# Seeeduino_v3_0.net
KiCad netlist of a schematic drawn in EAGLE
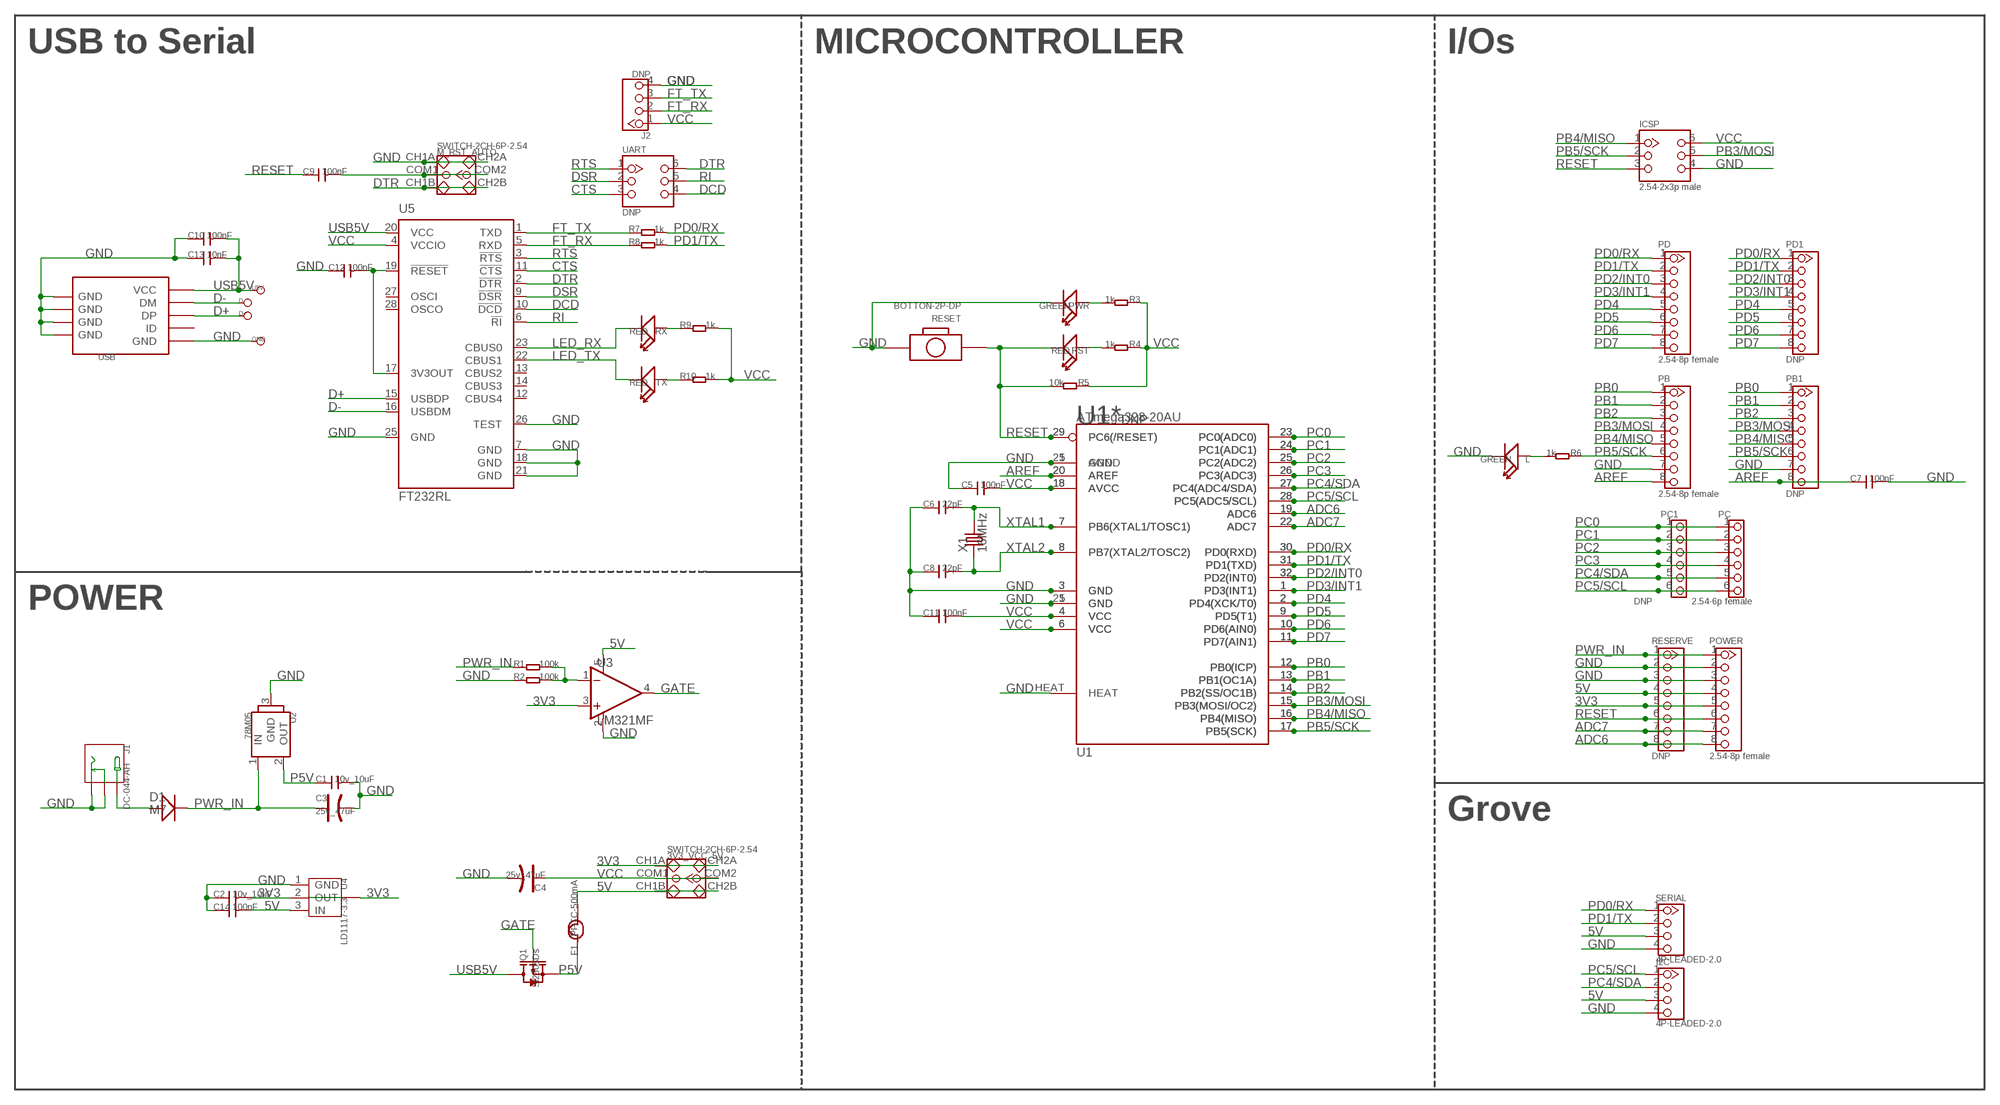
[diagram p0: schematic, sheet 1]

(export (version "E")
  (design (tool "Eeschema 10.0.6"))
  (components
    (comp (ref "3V3_VCC_5V")
      (value "SWITCH-2CH-6P-2.54")
      (footprint "eagle-import:6P-2CH-2.54-7.6X3.0")
      (libsource (lib "eagle-import") (part "SWITCH-2CH-6P"))
    )
    (comp (ref "C1")
      (value "10v_10uF")
      (footprint "eagle-import:0805")
      (libsource (lib "eagle-import") (part "C-0805"))
    )
    (comp (ref "C2")
      (value "10v_10uF")
      (footprint "eagle-import:0805")
      (libsource (lib "eagle-import") (part "C-0805"))
    )
    (comp (ref "C3")
      (value "25v_47uF")
      (footprint "eagle-import:ELECTRO-SMD-C-6MM")
      (libsource (lib "eagle-import") (part "CAP-ELECTRO-C"))
    )
    (comp (ref "C4")
      (value "25v_47uF")
      (footprint "eagle-import:ELECTRO-SMD-C-6MM")
      (libsource (lib "eagle-import") (part "CAP-ELECTRO-C"))
    )
    (comp (ref "C5")
      (value "100nF")
      (footprint "eagle-import:0603")
      (libsource (lib "eagle-import") (part "C-0603"))
    )
    (comp (ref "C6")
      (value "22pF")
      (footprint "eagle-import:0603")
      (libsource (lib "eagle-import") (part "C-0603"))
    )
    (comp (ref "C7")
      (value "100nF")
      (footprint "eagle-import:0603")
      (libsource (lib "eagle-import") (part "C-0603"))
    )
    (comp (ref "C8")
      (value "22pF")
      (footprint "eagle-import:0603")
      (libsource (lib "eagle-import") (part "C-0603"))
    )
    (comp (ref "C9")
      (value "100nF")
      (footprint "eagle-import:0603")
      (libsource (lib "eagle-import") (part "C-0603"))
    )
    (comp (ref "C10")
      (value "100nF")
      (footprint "eagle-import:0603")
      (libsource (lib "eagle-import") (part "C-0603"))
    )
    (comp (ref "C11")
      (value "100nF")
      (footprint "eagle-import:0603")
      (libsource (lib "eagle-import") (part "C-0603"))
    )
    (comp (ref "C12")
      (value "100nF")
      (footprint "eagle-import:0603")
      (libsource (lib "eagle-import") (part "C-0603"))
    )
    (comp (ref "C13")
      (value "10nF")
      (footprint "eagle-import:0603")
      (libsource (lib "eagle-import") (part "C-0603"))
    )
    (comp (ref "C14")
      (value "100nF")
      (footprint "eagle-import:0603")
      (libsource (lib "eagle-import") (part "C-0603"))
    )
    (comp (ref "D+")
      (value "TEST_POINT_SIZE_3030")
      (footprint "eagle-import:TP_3535")
      (libsource (lib "eagle-import") (part "TEST_POINT_SIZE_3030"))
    )
    (comp (ref "D-")
      (value "TEST_POINT_SIZE_3030")
      (footprint "eagle-import:TP_3535")
      (libsource (lib "eagle-import") (part "TEST_POINT_SIZE_3030"))
    )
    (comp (ref "D1")
      (value "M7")
      (footprint "eagle-import:D2010")
      (libsource (lib "eagle-import") (part "D-SMA"))
    )
    (comp (ref "F1")
      (value "PPTC-500mA")
      (footprint "eagle-import:1206")
      (libsource (lib "eagle-import") (part "FUSE"))
    )
    (comp (ref "GND")
      (value "TEST_POINT_SIZE_3030")
      (footprint "eagle-import:TP_3535")
      (libsource (lib "eagle-import") (part "TEST_POINT_SIZE_3030"))
    )
    (comp (ref "I2C")
      (value "4P-LEADED-2.0")
      (footprint "eagle-import:4P-LEADED-2.0")
      (libsource (lib "eagle-import") (part "TWIG-2.0-LEADED"))
    )
    (comp (ref "ICSP")
      (value "2.54-2x3p male")
      (footprint "eagle-import:2X3P-2.54")
      (libsource (lib "eagle-import") (part "HEADER-2X3P-2.54"))
    )
    (comp (ref "J1")
      (value "DC-044-AH")
      (footprint "eagle-import:DC-404")
      (libsource (lib "eagle-import") (part "DC-044"))
    )
    (comp (ref "J2")
      (value "DNP")
      (footprint "eagle-import:CK_1X4")
      (libsource (lib "eagle-import") (part "CK_1X4_DD"))
    )
    (comp (ref "L")
      (value "GREEN")
      (footprint "eagle-import:LED-0603")
      (libsource (lib "eagle-import") (part "LED'0603'"))
    )
    (comp (ref "M_RST_AUTO")
      (value "SWITCH-2CH-6P-2.54")
      (footprint "eagle-import:6P-2CH-2.54-7.6X3.0")
      (libsource (lib "eagle-import") (part "SWITCH-2CH-6P"))
    )
    (comp (ref "PB")
      (value "2.54-8p female")
      (footprint "eagle-import:8P-2.54")
      (libsource (lib "eagle-import") (part "HEADER-8P-2.54"))
    )
    (comp (ref "PB1")
      (value "DNP")
      (footprint "eagle-import:8P-2.54")
      (libsource (lib "eagle-import") (part "HEADER-8P-2.54"))
    )
    (comp (ref "PC")
      (value "2.54-6p female")
      (footprint "eagle-import:6P-2.54-65_35MIL")
      (libsource (lib "eagle-import") (part "HEADER-6P-65/35MIL"))
    )
    (comp (ref "PC1")
      (value "DNP")
      (footprint "eagle-import:6P-2.54-65_35MIL")
      (libsource (lib "eagle-import") (part "HEADER-6P-65/35MIL"))
    )
    (comp (ref "PD")
      (value "2.54-8p female")
      (footprint "eagle-import:8P-2.54")
      (libsource (lib "eagle-import") (part "HEADER-8P-2.54"))
    )
    (comp (ref "PD1")
      (value "DNP")
      (footprint "eagle-import:8P-2.54")
      (libsource (lib "eagle-import") (part "HEADER-8P-2.54"))
    )
    (comp (ref "POWER")
      (value "2.54-8p female")
      (footprint "eagle-import:8P-2.54")
      (libsource (lib "eagle-import") (part "HEADER-8P-2.54"))
    )
    (comp (ref "PWR")
      (value "GREEN")
      (footprint "eagle-import:LED-0603")
      (libsource (lib "eagle-import") (part "LED'0603'"))
    )
    (comp (ref "Q1")
      (value "Si2305Ds")
      (footprint "eagle-import:SOT23")
      (libsource (lib "eagle-import") (part "MOSFET-P-SOT23"))
    )
    (comp (ref "R1")
      (value "100k")
      (footprint "eagle-import:0603")
      (libsource (lib "eagle-import") (part "R-0603"))
    )
    (comp (ref "R2")
      (value "100k")
      (footprint "eagle-import:0603")
      (libsource (lib "eagle-import") (part "R-0603"))
    )
    (comp (ref "R3")
      (value "1k")
      (footprint "eagle-import:0603")
      (libsource (lib "eagle-import") (part "R-0603"))
    )
    (comp (ref "R4")
      (value "1k")
      (footprint "eagle-import:0603")
      (libsource (lib "eagle-import") (part "R-0603"))
    )
    (comp (ref "R5")
      (value "10k")
      (footprint "eagle-import:0603")
      (libsource (lib "eagle-import") (part "R-0603"))
    )
    (comp (ref "R6")
      (value "1k")
      (footprint "eagle-import:0603")
      (libsource (lib "eagle-import") (part "R-0603"))
    )
    (comp (ref "R7")
      (value "1k")
      (footprint "eagle-import:0603")
      (libsource (lib "eagle-import") (part "R-0603"))
    )
    (comp (ref "R8")
      (value "1k")
      (footprint "eagle-import:0603")
      (libsource (lib "eagle-import") (part "R-0603"))
    )
    (comp (ref "R9")
      (value "1k")
      (footprint "eagle-import:0603")
      (libsource (lib "eagle-import") (part "R-0603"))
    )
    (comp (ref "R10")
      (value "1k")
      (footprint "eagle-import:0603")
      (libsource (lib "eagle-import") (part "R-0603"))
    )
    (comp (ref "RESERVE")
      (value "DNP")
      (footprint "eagle-import:8P-2.54")
      (libsource (lib "eagle-import") (part "HEADER-8P-2.54"))
    )
    (comp (ref "RESET")
      (value "BOTTON-2P-DP")
      (footprint "eagle-import:2P-7.62X3.56-90D")
      (libsource (lib "eagle-import") (part "BOTTON-2P-90"))
    )
    (comp (ref "RST")
      (value "RED")
      (footprint "eagle-import:LED-0603")
      (libsource (lib "eagle-import") (part "LED'0603'"))
    )
    (comp (ref "RX")
      (value "RED")
      (footprint "eagle-import:LED-0603")
      (libsource (lib "eagle-import") (part "LED'0603'"))
    )
    (comp (ref "SERIAL")
      (value "4P-LEADED-2.0")
      (footprint "eagle-import:4P-LEADED-2.0")
      (libsource (lib "eagle-import") (part "TWIG-2.0-LEADED"))
    )
    (comp (ref "TX")
      (value "RED")
      (footprint "eagle-import:LED-0603")
      (libsource (lib "eagle-import") (part "LED'0603'"))
    )
    (comp (ref "U1")
      (value "ATmega328-20AU")
      (footprint "eagle-import:TQFP32")
      (libsource (lib "eagle-import") (part "ATMEGA168"))
    )
    (comp (ref "U1*")
      (value "DNP")
      (footprint "eagle-import:MLF32X")
      (libsource (lib "eagle-import") (part "MEGA8"))
    )
    (comp (ref "U2")
      (value "78M05")
      (footprint "eagle-import:TO252")
      (libsource (lib "eagle-import") (part "78M05-TO252"))
    )
    (comp (ref "U3")
      (value "LM321MF")
      (footprint "eagle-import:SOT23-5")
      (libsource (lib "eagle-import") (part "LM321"))
    )
    (comp (ref "U4")
      (value "LD1117-3.3")
      (footprint "eagle-import:SOT89")
      (libsource (lib "eagle-import") (part "LD1117SOT89"))
    )
    (comp (ref "U5")
      (value "FT232RL")
      (footprint "eagle-import:SSOP28")
      (libsource (lib "eagle-import") (part "FT232RL"))
    )
    (comp (ref "U5V")
      (value "TEST_POINT_SIZE_3030")
      (footprint "eagle-import:TP_3535")
      (libsource (lib "eagle-import") (part "TEST_POINT_SIZE_3030"))
    )
    (comp (ref "UART")
      (value "DNP")
      (footprint "eagle-import:2X3P-2.54")
      (libsource (lib "eagle-import") (part "HEADER-2X3P-2.54"))
    )
    (comp (ref "USB")
      (value "USB-MINIUSB-5P-STRONG")
      (footprint "eagle-import:MINI-SMD-5P")
      (libsource (lib "eagle-import") (part "USB-MINIUSB-5P-STRONG"))
    )
    (comp (ref "X1")
      (value "16MHz")
      (footprint "eagle-import:HC49_S")
      (libsource (lib "eagle-import") (part "CRYSTAL-HC49S"))
    )
  )
  (nets
    (net (code "1") (name "/3V3") (class "Default")
      (node (ref "3V3_VCC_5V") (pin "CH1A") (pinfunction "CH1A_CH1A") (pintype "bidirectional"))
      (node (ref "3V3_VCC_5V") (pin "CH2A") (pinfunction "CH2A_CH2A") (pintype "bidirectional"))
      (node (ref "C2") (pin "2") (pinfunction "2_2") (pintype "passive"))
      (node (ref "POWER") (pin "5") (pinfunction "5_5") (pintype "bidirectional"))
      (node (ref "RESERVE") (pin "5") (pinfunction "5_5") (pintype "bidirectional"))
      (node (ref "U3") (pin "3") (pinfunction "IN+_3") (pintype "input"))
      (node (ref "U4") (pin "2") (pinfunction "OUT_2") (pintype "bidirectional"))
      (node (ref "U4") (pin "4") (pinfunction "TAB_4") (pintype "bidirectional"))
    )
    (net (code "2") (name "/5V") (class "Default")
      (node (ref "3V3_VCC_5V") (pin "CH1B") (pinfunction "CH1B_CH1B") (pintype "bidirectional"))
      (node (ref "3V3_VCC_5V") (pin "CH2B") (pinfunction "CH2B_CH2B") (pintype "bidirectional"))
      (node (ref "C14") (pin "2") (pinfunction "2_2") (pintype "passive"))
      (node (ref "F1") (pin "2") (pinfunction "2_2") (pintype "bidirectional"))
      (node (ref "I2C") (pin "3") (pinfunction "3_3") (pintype "bidirectional"))
      (node (ref "POWER") (pin "4") (pinfunction "4_4") (pintype "bidirectional"))
      (node (ref "RESERVE") (pin "4") (pinfunction "4_4") (pintype "bidirectional"))
      (node (ref "SERIAL") (pin "3") (pinfunction "3_3") (pintype "bidirectional"))
      (node (ref "U3") (pin "5") (pinfunction "V+_5") (pintype "power_in"))
      (node (ref "U4") (pin "3") (pinfunction "IN_3") (pintype "bidirectional"))
    )
    (net (code "3") (name "/ADC6") (class "Default")
      (node (ref "POWER") (pin "8") (pinfunction "8_8") (pintype "bidirectional"))
      (node (ref "RESERVE") (pin "8") (pinfunction "8_8") (pintype "bidirectional"))
      (node (ref "U1") (pin "19") (pinfunction "ADC6_19") (pintype "bidirectional"))
      (node (ref "U1*") (pin "19") (pinfunction "ADC6_19") (pintype "bidirectional"))
    )
    (net (code "4") (name "/ADC7") (class "Default")
      (node (ref "POWER") (pin "7") (pinfunction "7_7") (pintype "bidirectional"))
      (node (ref "RESERVE") (pin "7") (pinfunction "7_7") (pintype "bidirectional"))
      (node (ref "U1") (pin "22") (pinfunction "ADC7_22") (pintype "bidirectional"))
      (node (ref "U1*") (pin "22") (pinfunction "ADC7_22") (pintype "bidirectional"))
    )
    (net (code "5") (name "/AREF") (class "Default")
      (node (ref "C7") (pin "1") (pinfunction "1_1") (pintype "passive"))
      (node (ref "PB") (pin "8") (pinfunction "8_8") (pintype "bidirectional"))
      (node (ref "PB1") (pin "8") (pinfunction "8_8") (pintype "bidirectional"))
      (node (ref "U1") (pin "20") (pinfunction "AREF_20") (pintype "bidirectional"))
      (node (ref "U1*") (pin "20") (pinfunction "AREF_20") (pintype "bidirectional"))
    )
    (net (code "6") (name "/CTS") (class "Default")
      (node (ref "U5") (pin "11") (pinfunction "~{CTS}_11") (pintype "input"))
      (node (ref "UART") (pin "3") (pinfunction "3_3") (pintype "bidirectional"))
    )
    (net (code "7") (name "/D+") (class "Default")
      (node (ref "D+") (pin "T") (pinfunction "T_T") (pintype "bidirectional"))
      (node (ref "U5") (pin "15") (pinfunction "USBDP_15") (pintype "input"))
      (node (ref "USB") (pin "3") (pinfunction "DP_3") (pintype "bidirectional"))
    )
    (net (code "8") (name "/D-") (class "Default")
      (node (ref "D-") (pin "T") (pinfunction "T_T") (pintype "bidirectional"))
      (node (ref "U5") (pin "16") (pinfunction "USBDM_16") (pintype "input"))
      (node (ref "USB") (pin "2") (pinfunction "DM_2") (pintype "bidirectional"))
    )
    (net (code "9") (name "/DCD") (class "Default")
      (node (ref "U5") (pin "10") (pinfunction "~{DCD}_10") (pintype "input"))
      (node (ref "UART") (pin "4") (pinfunction "4_4") (pintype "bidirectional"))
    )
    (net (code "10") (name "/DSR") (class "Default")
      (node (ref "U5") (pin "9") (pinfunction "~{DSR}_9") (pintype "input"))
      (node (ref "UART") (pin "2") (pinfunction "2_2") (pintype "bidirectional"))
    )
    (net (code "11") (name "/DTR") (class "Default")
      (node (ref "M_RST_AUTO") (pin "CH1B") (pinfunction "CH1B_CH1B") (pintype "bidirectional"))
      (node (ref "M_RST_AUTO") (pin "CH2B") (pinfunction "CH2B_CH2B") (pintype "bidirectional"))
      (node (ref "U5") (pin "2") (pinfunction "~{DTR}_2") (pintype "input"))
      (node (ref "UART") (pin "6") (pinfunction "6_6") (pintype "bidirectional"))
    )
    (net (code "12") (name "/FT_RX") (class "Default")
      (node (ref "J2") (pin "2") (pinfunction "P$2_2") (pintype "bidirectional"))
      (node (ref "R8") (pin "1") (pinfunction "1_1") (pintype "passive"))
      (node (ref "U5") (pin "5") (pinfunction "RXD_5") (pintype "input"))
    )
    (net (code "13") (name "/FT_TX") (class "Default")
      (node (ref "J2") (pin "3") (pinfunction "P$3_3") (pintype "bidirectional"))
      (node (ref "R7") (pin "1") (pinfunction "1_1") (pintype "passive"))
      (node (ref "U5") (pin "1") (pinfunction "TXD_1") (pintype "input"))
    )
    (net (code "14") (name "/GATE") (class "Default")
      (node (ref "Q1") (pin "1") (pinfunction "G_1") (pintype "passive"))
      (node (ref "U3") (pin "4") (pinfunction "OUT_4") (pintype "output"))
    )
    (net (code "15") (name "/GND") (class "Default")
      (node (ref "C1") (pin "2") (pinfunction "2_2") (pintype "passive"))
      (node (ref "C10") (pin "1") (pinfunction "1_1") (pintype "passive"))
      (node (ref "C11") (pin "1") (pinfunction "1_1") (pintype "passive"))
      (node (ref "C12") (pin "1") (pinfunction "1_1") (pintype "passive"))
      (node (ref "C13") (pin "1") (pinfunction "1_1") (pintype "passive"))
      (node (ref "C14") (pin "1") (pinfunction "1_1") (pintype "passive"))
      (node (ref "C2") (pin "1") (pinfunction "1_1") (pintype "passive"))
      (node (ref "C3") (pin "-") (pinfunction "-_-") (pintype "passive"))
      (node (ref "C4") (pin "-") (pinfunction "-_-") (pintype "passive"))
      (node (ref "C5") (pin "1") (pinfunction "1_1") (pintype "passive"))
      (node (ref "C6") (pin "1") (pinfunction "1_1") (pintype "passive"))
      (node (ref "C7") (pin "2") (pinfunction "2_2") (pintype "passive"))
      (node (ref "C8") (pin "1") (pinfunction "1_1") (pintype "passive"))
      (node (ref "GND") (pin "T") (pinfunction "T_T") (pintype "bidirectional"))
      (node (ref "I2C") (pin "4") (pinfunction "4_4") (pintype "bidirectional"))
      (node (ref "ICSP") (pin "4") (pinfunction "4_4") (pintype "bidirectional"))
      (node (ref "J1") (pin "-") (pinfunction "-_-") (pintype "bidirectional"))
      (node (ref "J1") (pin "CDN") (pinfunction "CDN_CDN") (pintype "bidirectional"))
      (node (ref "J2") (pin "4") (pinfunction "P$4_4") (pintype "bidirectional"))
      (node (ref "L") (pin "-") (pinfunction "-_-") (pintype "passive"))
      (node (ref "M_RST_AUTO") (pin "CH1A") (pinfunction "CH1A_CH1A") (pintype "bidirectional"))
      (node (ref "M_RST_AUTO") (pin "CH2A") (pinfunction "CH2A_CH2A") (pintype "bidirectional"))
      (node (ref "PB") (pin "7") (pinfunction "7_7") (pintype "bidirectional"))
      (node (ref "PB1") (pin "7") (pinfunction "7_7") (pintype "bidirectional"))
      (node (ref "POWER") (pin "2") (pinfunction "2_2") (pintype "bidirectional"))
      (node (ref "POWER") (pin "3") (pinfunction "3_3") (pintype "bidirectional"))
      (node (ref "PWR") (pin "-") (pinfunction "-_-") (pintype "passive"))
      (node (ref "R2") (pin "1") (pinfunction "1_1") (pintype "passive"))
      (node (ref "RESERVE") (pin "2") (pinfunction "2_2") (pintype "bidirectional"))
      (node (ref "RESERVE") (pin "3") (pinfunction "3_3") (pintype "bidirectional"))
      (node (ref "RESET") (pin "P$2") (pinfunction "2_P$2") (pintype "bidirectional"))
      (node (ref "SERIAL") (pin "4") (pinfunction "4_4") (pintype "bidirectional"))
      (node (ref "U1") (pin "21") (pinfunction "GND_21") (pintype "bidirectional"))
      (node (ref "U1") (pin "3") (pinfunction "GND_3") (pintype "bidirectional"))
      (node (ref "U1") (pin "5") (pinfunction "GND_5") (pintype "bidirectional"))
      (node (ref "U1*") (pin "21") (pinfunction "AGND_21") (pintype "bidirectional"))
      (node (ref "U1*") (pin "3") (pinfunction "GND_3") (pintype "bidirectional"))
      (node (ref "U1*") (pin "5") (pinfunction "GND_5") (pintype "bidirectional"))
      (node (ref "U1*") (pin "HEAT") (pinfunction "HEAT_HEAT") (pintype "bidirectional"))
      (node (ref "U2") (pin "3") (pinfunction "GND_3") (pintype "bidirectional"))
      (node (ref "U3") (pin "2") (pinfunction "V-_2") (pintype "power_in"))
      (node (ref "U4") (pin "1") (pinfunction "GND_1") (pintype "bidirectional"))
      (node (ref "U5") (pin "18") (pinfunction "GND_18") (pintype "input"))
      (node (ref "U5") (pin "21") (pinfunction "GND_21") (pintype "input"))
      (node (ref "U5") (pin "25") (pinfunction "GND_25") (pintype "input"))
      (node (ref "U5") (pin "26") (pinfunction "TEST_26") (pintype "input"))
      (node (ref "U5") (pin "7") (pinfunction "GND_7") (pintype "input"))
      (node (ref "USB") (pin "5") (pinfunction "GND_5") (pintype "bidirectional"))
      (node (ref "USB") (pin "GND@1") (pinfunction "GND_GND@1") (pintype "bidirectional"))
      (node (ref "USB") (pin "GND@2") (pinfunction "GND_GND@2") (pintype "bidirectional"))
      (node (ref "USB") (pin "GND@3") (pinfunction "GND_GND@3") (pintype "bidirectional"))
      (node (ref "USB") (pin "GND@4") (pinfunction "GND_GND@4") (pintype "bidirectional"))
    )
    (net (code "16") (name "/LED_RX") (class "Default")
      (node (ref "RX") (pin "-") (pinfunction "-_-") (pintype "passive"))
      (node (ref "U5") (pin "23") (pinfunction "CBUS0_23") (pintype "input"))
    )
    (net (code "17") (name "/LED_TX") (class "Default")
      (node (ref "TX") (pin "-") (pinfunction "-_-") (pintype "passive"))
      (node (ref "U5") (pin "22") (pinfunction "CBUS1_22") (pintype "input"))
    )
    (net (code "18") (name "/P5V") (class "Default")
      (node (ref "C1") (pin "1") (pinfunction "1_1") (pintype "passive"))
      (node (ref "F1") (pin "1") (pinfunction "1_1") (pintype "bidirectional"))
      (node (ref "Q1") (pin "2") (pinfunction "S_2") (pintype "passive"))
      (node (ref "U2") (pin "2") (pinfunction "OUT_2") (pintype "bidirectional"))
    )
    (net (code "19") (name "/PB0") (class "Default")
      (node (ref "PB") (pin "1") (pinfunction "1_1") (pintype "bidirectional"))
      (node (ref "PB1") (pin "1") (pinfunction "1_1") (pintype "bidirectional"))
      (node (ref "U1") (pin "12") (pinfunction "PB0(ICP)_12") (pintype "bidirectional"))
      (node (ref "U1*") (pin "12") (pinfunction "PB0(ICP)_12") (pintype "bidirectional"))
    )
    (net (code "20") (name "/PB1") (class "Default")
      (node (ref "PB") (pin "2") (pinfunction "2_2") (pintype "bidirectional"))
      (node (ref "PB1") (pin "2") (pinfunction "2_2") (pintype "bidirectional"))
      (node (ref "U1") (pin "13") (pinfunction "PB1(OC1A)_13") (pintype "bidirectional"))
      (node (ref "U1*") (pin "13") (pinfunction "PB1(OC1A)_13") (pintype "bidirectional"))
    )
    (net (code "21") (name "/PB2") (class "Default")
      (node (ref "PB") (pin "3") (pinfunction "3_3") (pintype "bidirectional"))
      (node (ref "PB1") (pin "3") (pinfunction "3_3") (pintype "bidirectional"))
      (node (ref "U1") (pin "14") (pinfunction "PB2(SS/OC1B)_14") (pintype "bidirectional"))
      (node (ref "U1*") (pin "14") (pinfunction "PB2(SS/OC1B)_14") (pintype "bidirectional"))
    )
    (net (code "22") (name "/PB3{slash}MOSI") (class "Default")
      (node (ref "ICSP") (pin "5") (pinfunction "5_5") (pintype "bidirectional"))
      (node (ref "PB") (pin "4") (pinfunction "4_4") (pintype "bidirectional"))
      (node (ref "PB1") (pin "4") (pinfunction "4_4") (pintype "bidirectional"))
      (node (ref "U1") (pin "15") (pinfunction "PB3(MOSI/OC2)_15") (pintype "bidirectional"))
      (node (ref "U1*") (pin "15") (pinfunction "PB3(MOSI/OC2)_15") (pintype "bidirectional"))
    )
    (net (code "23") (name "/PB4{slash}MISO") (class "Default")
      (node (ref "ICSP") (pin "1") (pinfunction "1_1") (pintype "bidirectional"))
      (node (ref "PB") (pin "5") (pinfunction "5_5") (pintype "bidirectional"))
      (node (ref "PB1") (pin "5") (pinfunction "5_5") (pintype "bidirectional"))
      (node (ref "U1") (pin "16") (pinfunction "PB4(MISO)_16") (pintype "bidirectional"))
      (node (ref "U1*") (pin "16") (pinfunction "PB4(MISO)_16") (pintype "bidirectional"))
    )
    (net (code "24") (name "/PB5{slash}SCK") (class "Default")
      (node (ref "ICSP") (pin "2") (pinfunction "2_2") (pintype "bidirectional"))
      (node (ref "PB") (pin "6") (pinfunction "6_6") (pintype "bidirectional"))
      (node (ref "PB1") (pin "6") (pinfunction "6_6") (pintype "bidirectional"))
      (node (ref "R6") (pin "1") (pinfunction "1_1") (pintype "passive"))
      (node (ref "U1") (pin "17") (pinfunction "PB5(SCK)_17") (pintype "bidirectional"))
      (node (ref "U1*") (pin "17") (pinfunction "PB5(SCK)_17") (pintype "bidirectional"))
    )
    (net (code "25") (name "/PC0") (class "Default")
      (node (ref "PC") (pin "1") (pinfunction "1_1") (pintype "bidirectional"))
      (node (ref "PC1") (pin "1") (pinfunction "1_1") (pintype "bidirectional"))
      (node (ref "U1") (pin "23") (pinfunction "PC0(ADC0)_23") (pintype "bidirectional"))
      (node (ref "U1*") (pin "23") (pinfunction "PC0(ADC0)_23") (pintype "bidirectional"))
    )
    (net (code "26") (name "/PC1") (class "Default")
      (node (ref "PC") (pin "2") (pinfunction "2_2") (pintype "bidirectional"))
      (node (ref "PC1") (pin "2") (pinfunction "2_2") (pintype "bidirectional"))
      (node (ref "U1") (pin "24") (pinfunction "PC1(ADC1)_24") (pintype "bidirectional"))
      (node (ref "U1*") (pin "24") (pinfunction "PC1(ADC1)_24") (pintype "bidirectional"))
    )
    (net (code "27") (name "/PC2") (class "Default")
      (node (ref "PC") (pin "3") (pinfunction "3_3") (pintype "bidirectional"))
      (node (ref "PC1") (pin "3") (pinfunction "3_3") (pintype "bidirectional"))
      (node (ref "U1") (pin "25") (pinfunction "PC2(ADC2)_25") (pintype "bidirectional"))
      (node (ref "U1*") (pin "25") (pinfunction "PC2(ADC2)_25") (pintype "bidirectional"))
    )
    (net (code "28") (name "/PC3") (class "Default")
      (node (ref "PC") (pin "4") (pinfunction "4_4") (pintype "bidirectional"))
      (node (ref "PC1") (pin "4") (pinfunction "4_4") (pintype "bidirectional"))
      (node (ref "U1") (pin "26") (pinfunction "PC3(ADC3)_26") (pintype "bidirectional"))
      (node (ref "U1*") (pin "26") (pinfunction "PC3(ADC3)_26") (pintype "bidirectional"))
    )
    (net (code "29") (name "/PC4{slash}SDA") (class "Default")
      (node (ref "I2C") (pin "2") (pinfunction "2_2") (pintype "bidirectional"))
      (node (ref "PC") (pin "5") (pinfunction "5_5") (pintype "bidirectional"))
      (node (ref "PC1") (pin "5") (pinfunction "5_5") (pintype "bidirectional"))
      (node (ref "U1") (pin "27") (pinfunction "PC4(ADC4/SDA)_27") (pintype "bidirectional"))
      (node (ref "U1*") (pin "27") (pinfunction "PC4(ADC4/SDA)_27") (pintype "bidirectional"))
    )
    (net (code "30") (name "/PC5{slash}SCL") (class "Default")
      (node (ref "I2C") (pin "1") (pinfunction "1_1") (pintype "bidirectional"))
      (node (ref "PC") (pin "6") (pinfunction "6_6") (pintype "bidirectional"))
      (node (ref "PC1") (pin "6") (pinfunction "6_6") (pintype "bidirectional"))
      (node (ref "U1") (pin "28") (pinfunction "PC5(ADC5/SCL)_28") (pintype "bidirectional"))
      (node (ref "U1*") (pin "28") (pinfunction "PC5(ADC5/SCL)_28") (pintype "bidirectional"))
    )
    (net (code "31") (name "/PD0{slash}RX") (class "Default")
      (node (ref "PD") (pin "1") (pinfunction "1_1") (pintype "bidirectional"))
      (node (ref "PD1") (pin "1") (pinfunction "1_1") (pintype "bidirectional"))
      (node (ref "R7") (pin "2") (pinfunction "2_2") (pintype "passive"))
      (node (ref "SERIAL") (pin "1") (pinfunction "1_1") (pintype "bidirectional"))
      (node (ref "U1") (pin "30") (pinfunction "PD0(RXD)_30") (pintype "bidirectional"))
      (node (ref "U1*") (pin "30") (pinfunction "PD0(RXD)_30") (pintype "bidirectional"))
    )
    (net (code "32") (name "/PD1{slash}TX") (class "Default")
      (node (ref "PD") (pin "2") (pinfunction "2_2") (pintype "bidirectional"))
      (node (ref "PD1") (pin "2") (pinfunction "2_2") (pintype "bidirectional"))
      (node (ref "R8") (pin "2") (pinfunction "2_2") (pintype "passive"))
      (node (ref "SERIAL") (pin "2") (pinfunction "2_2") (pintype "bidirectional"))
      (node (ref "U1") (pin "31") (pinfunction "PD1(TXD)_31") (pintype "bidirectional"))
      (node (ref "U1*") (pin "31") (pinfunction "PD1(TXD)_31") (pintype "bidirectional"))
    )
    (net (code "33") (name "/PD2{slash}INT0") (class "Default")
      (node (ref "PD") (pin "3") (pinfunction "3_3") (pintype "bidirectional"))
      (node (ref "PD1") (pin "3") (pinfunction "3_3") (pintype "bidirectional"))
      (node (ref "U1") (pin "32") (pinfunction "PD2(INT0)_32") (pintype "bidirectional"))
      (node (ref "U1*") (pin "32") (pinfunction "PD2(INT0)_32") (pintype "bidirectional"))
    )
    (net (code "34") (name "/PD3{slash}INT1") (class "Default")
      (node (ref "PD") (pin "4") (pinfunction "4_4") (pintype "bidirectional"))
      (node (ref "PD1") (pin "4") (pinfunction "4_4") (pintype "bidirectional"))
      (node (ref "U1") (pin "1") (pinfunction "PD3(INT1)_1") (pintype "bidirectional"))
      (node (ref "U1*") (pin "1") (pinfunction "PD3(INT1)_1") (pintype "bidirectional"))
    )
    (net (code "35") (name "/PD4") (class "Default")
      (node (ref "PD") (pin "5") (pinfunction "5_5") (pintype "bidirectional"))
      (node (ref "PD1") (pin "5") (pinfunction "5_5") (pintype "bidirectional"))
      (node (ref "U1") (pin "2") (pinfunction "PD4(XCK/T0)_2") (pintype "bidirectional"))
      (node (ref "U1*") (pin "2") (pinfunction "PD4(XCK/T0)_2") (pintype "bidirectional"))
    )
    (net (code "36") (name "/PD5") (class "Default")
      (node (ref "PD") (pin "6") (pinfunction "6_6") (pintype "bidirectional"))
      (node (ref "PD1") (pin "6") (pinfunction "6_6") (pintype "bidirectional"))
      (node (ref "U1") (pin "9") (pinfunction "PD5(T1)_9") (pintype "bidirectional"))
      (node (ref "U1*") (pin "9") (pinfunction "PD5(T1)_9") (pintype "bidirectional"))
    )
    (net (code "37") (name "/PD6") (class "Default")
      (node (ref "PD") (pin "7") (pinfunction "7_7") (pintype "bidirectional"))
      (node (ref "PD1") (pin "7") (pinfunction "7_7") (pintype "bidirectional"))
      (node (ref "U1") (pin "10") (pinfunction "PD6(AIN0)_10") (pintype "bidirectional"))
      (node (ref "U1*") (pin "10") (pinfunction "PD6(AIN0)_10") (pintype "bidirectional"))
    )
    (net (code "38") (name "/PD7") (class "Default")
      (node (ref "PD") (pin "8") (pinfunction "8_8") (pintype "bidirectional"))
      (node (ref "PD1") (pin "8") (pinfunction "8_8") (pintype "bidirectional"))
      (node (ref "U1") (pin "11") (pinfunction "PD7(AIN1)_11") (pintype "bidirectional"))
      (node (ref "U1*") (pin "11") (pinfunction "PD7(AIN1)_11") (pintype "bidirectional"))
    )
    (net (code "39") (name "/PWR_IN") (class "Default")
      (node (ref "C3") (pin "+") (pinfunction "+_+") (pintype "passive"))
      (node (ref "D1") (pin "-") (pinfunction "-_-") (pintype "passive"))
      (node (ref "POWER") (pin "1") (pinfunction "1_1") (pintype "bidirectional"))
      (node (ref "R1") (pin "1") (pinfunction "1_1") (pintype "passive"))
      (node (ref "RESERVE") (pin "1") (pinfunction "1_1") (pintype "bidirectional"))
      (node (ref "U2") (pin "1") (pinfunction "IN_1") (pintype "bidirectional"))
    )
    (net (code "40") (name "/RESET") (class "Default")
      (node (ref "C9") (pin "1") (pinfunction "1_1") (pintype "passive"))
      (node (ref "ICSP") (pin "3") (pinfunction "3_3") (pintype "bidirectional"))
      (node (ref "POWER") (pin "6") (pinfunction "6_6") (pintype "bidirectional"))
      (node (ref "R5") (pin "2") (pinfunction "2_2") (pintype "passive"))
      (node (ref "RESERVE") (pin "6") (pinfunction "6_6") (pintype "bidirectional"))
      (node (ref "RESET") (pin "P$1") (pinfunction "1_P$1") (pintype "bidirectional"))
      (node (ref "RST") (pin "-") (pinfunction "-_-") (pintype "passive"))
      (node (ref "U1") (pin "29") (pinfunction "PC6(/RESET)_29") (pintype "bidirectional"))
      (node (ref "U1*") (pin "29") (pinfunction "PC6(/RESET)_29") (pintype "bidirectional"))
    )
    (net (code "41") (name "/RI") (class "Default")
      (node (ref "U5") (pin "6") (pinfunction "~{RI}_6") (pintype "input"))
      (node (ref "UART") (pin "5") (pinfunction "5_5") (pintype "bidirectional"))
    )
    (net (code "42") (name "/RTS") (class "Default")
      (node (ref "U5") (pin "3") (pinfunction "~{RTS}_3") (pintype "input"))
      (node (ref "UART") (pin "1") (pinfunction "1_1") (pintype "bidirectional"))
    )
    (net (code "43") (name "/USB5V") (class "Default")
      (node (ref "C10") (pin "2") (pinfunction "2_2") (pintype "passive"))
      (node (ref "C13") (pin "2") (pinfunction "2_2") (pintype "passive"))
      (node (ref "Q1") (pin "3") (pinfunction "D_3") (pintype "passive"))
      (node (ref "U5") (pin "20") (pinfunction "VCC_20") (pintype "input"))
      (node (ref "U5V") (pin "T") (pinfunction "T_T") (pintype "bidirectional"))
      (node (ref "USB") (pin "1") (pinfunction "VCC_1") (pintype "bidirectional"))
    )
    (net (code "44") (name "/VCC") (class "Default")
      (node (ref "3V3_VCC_5V") (pin "COM1") (pinfunction "COM1_COM1") (pintype "bidirectional"))
      (node (ref "3V3_VCC_5V") (pin "COM2") (pinfunction "COM2_COM2") (pintype "bidirectional"))
      (node (ref "C11") (pin "2") (pinfunction "2_2") (pintype "passive"))
      (node (ref "C4") (pin "+") (pinfunction "+_+") (pintype "passive"))
      (node (ref "C5") (pin "2") (pinfunction "2_2") (pintype "passive"))
      (node (ref "ICSP") (pin "6") (pinfunction "6_6") (pintype "bidirectional"))
      (node (ref "J2") (pin "1") (pinfunction "P$1_1") (pintype "bidirectional"))
      (node (ref "R10") (pin "2") (pinfunction "2_2") (pintype "passive"))
      (node (ref "R3") (pin "1") (pinfunction "1_1") (pintype "passive"))
      (node (ref "R4") (pin "1") (pinfunction "1_1") (pintype "passive"))
      (node (ref "R5") (pin "1") (pinfunction "1_1") (pintype "passive"))
      (node (ref "R9") (pin "2") (pinfunction "2_2") (pintype "passive"))
      (node (ref "U1") (pin "18") (pinfunction "AVCC_18") (pintype "bidirectional"))
      (node (ref "U1") (pin "4") (pinfunction "VCC_4") (pintype "bidirectional"))
      (node (ref "U1") (pin "6") (pinfunction "VCC_6") (pintype "bidirectional"))
      (node (ref "U1*") (pin "18") (pinfunction "AVCC_18") (pintype "bidirectional"))
      (node (ref "U1*") (pin "4") (pinfunction "VCC_4") (pintype "bidirectional"))
      (node (ref "U1*") (pin "6") (pinfunction "VCC_6") (pintype "bidirectional"))
      (node (ref "U5") (pin "4") (pinfunction "VCCIO_4") (pintype "input"))
    )
    (net (code "45") (name "/XTAL1") (class "Default")
      (node (ref "C6") (pin "2") (pinfunction "2_2") (pintype "passive"))
      (node (ref "U1") (pin "7") (pinfunction "PB6(XTAL1/TOSC1)_7") (pintype "bidirectional"))
      (node (ref "U1*") (pin "7") (pinfunction "PB6(XTAL1/TOSC1)_7") (pintype "bidirectional"))
      (node (ref "X1") (pin "2") (pinfunction "2_2") (pintype "passive"))
    )
    (net (code "46") (name "/XTAL2") (class "Default")
      (node (ref "C8") (pin "2") (pinfunction "2_2") (pintype "passive"))
      (node (ref "U1") (pin "8") (pinfunction "PB7(XTAL2/TOSC2)_8") (pintype "bidirectional"))
      (node (ref "U1*") (pin "8") (pinfunction "PB7(XTAL2/TOSC2)_8") (pintype "bidirectional"))
      (node (ref "X1") (pin "1") (pinfunction "1_1") (pintype "passive"))
    )
    (net (code "47") (name "Net-(C9-Pad2)") (class "Default")
      (node (ref "C9") (pin "2") (pinfunction "2_2") (pintype "passive"))
      (node (ref "M_RST_AUTO") (pin "COM1") (pinfunction "COM1_COM1") (pintype "bidirectional"))
      (node (ref "M_RST_AUTO") (pin "COM2") (pinfunction "COM2_COM2") (pintype "bidirectional"))
    )
    (net (code "48") (name "Net-(D1-Pad+)") (class "Default")
      (node (ref "D1") (pin "+") (pinfunction "+_+") (pintype "passive"))
      (node (ref "J1") (pin "+") (pinfunction "+_+") (pintype "bidirectional"))
    )
    (net (code "49") (name "Net-(L-Pad+)") (class "Default")
      (node (ref "L") (pin "+") (pinfunction "+_+") (pintype "passive"))
      (node (ref "R6") (pin "2") (pinfunction "2_2") (pintype "passive"))
    )
    (net (code "50") (name "Net-(PWR-Pad+)") (class "Default")
      (node (ref "PWR") (pin "+") (pinfunction "+_+") (pintype "passive"))
      (node (ref "R3") (pin "2") (pinfunction "2_2") (pintype "passive"))
    )
    (net (code "51") (name "Net-(R4-Pad2)") (class "Default")
      (node (ref "R4") (pin "2") (pinfunction "2_2") (pintype "passive"))
      (node (ref "RST") (pin "+") (pinfunction "+_+") (pintype "passive"))
    )
    (net (code "52") (name "Net-(R9-Pad1)") (class "Default")
      (node (ref "R9") (pin "1") (pinfunction "1_1") (pintype "passive"))
      (node (ref "RX") (pin "+") (pinfunction "+_+") (pintype "passive"))
    )
    (net (code "53") (name "Net-(R10-Pad1)") (class "Default")
      (node (ref "R10") (pin "1") (pinfunction "1_1") (pintype "passive"))
      (node (ref "TX") (pin "+") (pinfunction "+_+") (pintype "passive"))
    )
    (net (code "54") (name "Net-(U3-IN-)") (class "Default")
      (node (ref "R1") (pin "2") (pinfunction "2_2") (pintype "passive"))
      (node (ref "R2") (pin "2") (pinfunction "2_2") (pintype "passive"))
      (node (ref "U3") (pin "1") (pinfunction "IN-_1") (pintype "input"))
    )
    (net (code "55") (name "Net-(U5-3V3OUT)") (class "Default")
      (node (ref "C12") (pin "2") (pinfunction "2_2") (pintype "passive"))
      (node (ref "U5") (pin "17") (pinfunction "3V3OUT_17") (pintype "input"))
      (node (ref "U5") (pin "19") (pinfunction "~{RESET}_19") (pintype "input"))
    )
    (net (code "56") (name "unconnected-(U5-CBUS2-Pad13)") (class "Default")
      (node (ref "U5") (pin "13") (pinfunction "CBUS2_13") (pintype "input"))
    )
    (net (code "57") (name "unconnected-(U5-CBUS3-Pad14)") (class "Default")
      (node (ref "U5") (pin "14") (pinfunction "CBUS3_14") (pintype "input"))
    )
    (net (code "58") (name "unconnected-(U5-CBUS4-Pad12)") (class "Default")
      (node (ref "U5") (pin "12") (pinfunction "CBUS4_12") (pintype "input"))
    )
    (net (code "59") (name "unconnected-(U5-OSCI-Pad27)") (class "Default")
      (node (ref "U5") (pin "27") (pinfunction "OSCI_27") (pintype "input"))
    )
    (net (code "60") (name "unconnected-(U5-OSCO-Pad28)") (class "Default")
      (node (ref "U5") (pin "28") (pinfunction "OSCO_28") (pintype "input"))
    )
    (net (code "61") (name "unconnected-(USB-ID-Pad4)") (class "Default")
      (node (ref "USB") (pin "4") (pinfunction "ID_4") (pintype "bidirectional"))
    )
  )
)
